# Rev1_0.net
KiCad netlist of a schematic drawn in EAGLE
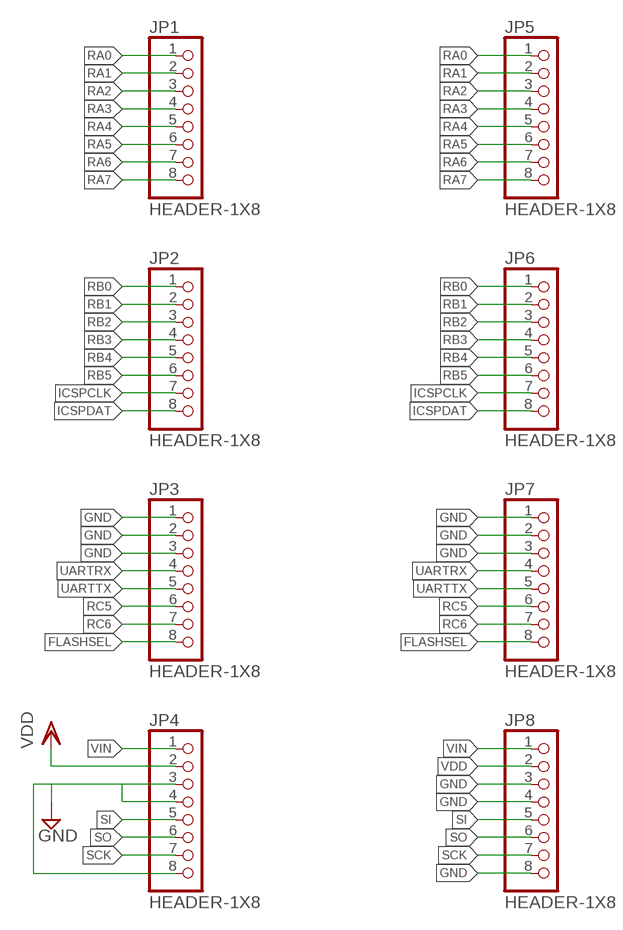
[diagram p0: schematic, sheet 1]

(export (version "E")
  (design (tool "Eeschema 10.0.6"))
  (components
    (comp (ref "JP1")
      (value "HEADER-1X8")
      (footprint "eagle-import:1X08")
      (libsource (lib "eagle-import") (part "HEADER-1X8"))
    )
    (comp (ref "JP2")
      (value "HEADER-1X8")
      (footprint "eagle-import:1X08")
      (libsource (lib "eagle-import") (part "HEADER-1X8"))
    )
    (comp (ref "JP3")
      (value "HEADER-1X8")
      (footprint "eagle-import:1X08")
      (libsource (lib "eagle-import") (part "HEADER-1X8"))
    )
    (comp (ref "JP4")
      (value "HEADER-1X8")
      (footprint "eagle-import:1X08")
      (libsource (lib "eagle-import") (part "HEADER-1X8"))
    )
    (comp (ref "JP5")
      (value "HEADER-1X8")
      (footprint "eagle-import:1X08")
      (libsource (lib "eagle-import") (part "HEADER-1X8"))
    )
    (comp (ref "JP6")
      (value "HEADER-1X8")
      (footprint "eagle-import:1X08")
      (libsource (lib "eagle-import") (part "HEADER-1X8"))
    )
    (comp (ref "JP7")
      (value "HEADER-1X8")
      (footprint "eagle-import:1X08")
      (libsource (lib "eagle-import") (part "HEADER-1X8"))
    )
    (comp (ref "JP8")
      (value "HEADER-1X8")
      (footprint "eagle-import:1X08")
      (libsource (lib "eagle-import") (part "HEADER-1X8"))
    )
  )
  (nets
    (net (code "1") (name "FLASHSEL") (class "Default")
      (node (ref "JP3") (pin "8") (pinfunction "8_8") (pintype "passive"))
      (node (ref "JP7") (pin "8") (pinfunction "8_8") (pintype "passive"))
    )
    (net (code "2") (name "GND") (class "Default")
      (node (ref "JP3") (pin "1") (pinfunction "1_1") (pintype "passive"))
      (node (ref "JP3") (pin "2") (pinfunction "2_2") (pintype "passive"))
      (node (ref "JP3") (pin "3") (pinfunction "3_3") (pintype "passive"))
      (node (ref "JP4") (pin "3") (pinfunction "3_3") (pintype "passive"))
      (node (ref "JP4") (pin "4") (pinfunction "4_4") (pintype "passive"))
      (node (ref "JP4") (pin "8") (pinfunction "8_8") (pintype "passive"))
      (node (ref "JP7") (pin "1") (pinfunction "1_1") (pintype "passive"))
      (node (ref "JP7") (pin "2") (pinfunction "2_2") (pintype "passive"))
      (node (ref "JP7") (pin "3") (pinfunction "3_3") (pintype "passive"))
      (node (ref "JP8") (pin "3") (pinfunction "3_3") (pintype "passive"))
      (node (ref "JP8") (pin "4") (pinfunction "4_4") (pintype "passive"))
      (node (ref "JP8") (pin "8") (pinfunction "8_8") (pintype "passive"))
    )
    (net (code "3") (name "ICSPCLK") (class "Default")
      (node (ref "JP2") (pin "7") (pinfunction "7_7") (pintype "passive"))
      (node (ref "JP6") (pin "7") (pinfunction "7_7") (pintype "passive"))
    )
    (net (code "4") (name "ICSPDAT") (class "Default")
      (node (ref "JP2") (pin "8") (pinfunction "8_8") (pintype "passive"))
      (node (ref "JP6") (pin "8") (pinfunction "8_8") (pintype "passive"))
    )
    (net (code "5") (name "RA0") (class "Default")
      (node (ref "JP1") (pin "1") (pinfunction "1_1") (pintype "passive"))
      (node (ref "JP5") (pin "1") (pinfunction "1_1") (pintype "passive"))
    )
    (net (code "6") (name "RA1") (class "Default")
      (node (ref "JP1") (pin "2") (pinfunction "2_2") (pintype "passive"))
      (node (ref "JP5") (pin "2") (pinfunction "2_2") (pintype "passive"))
    )
    (net (code "7") (name "RA2") (class "Default")
      (node (ref "JP1") (pin "3") (pinfunction "3_3") (pintype "passive"))
      (node (ref "JP5") (pin "3") (pinfunction "3_3") (pintype "passive"))
    )
    (net (code "8") (name "RA3") (class "Default")
      (node (ref "JP1") (pin "4") (pinfunction "4_4") (pintype "passive"))
      (node (ref "JP5") (pin "4") (pinfunction "4_4") (pintype "passive"))
    )
    (net (code "9") (name "RA4") (class "Default")
      (node (ref "JP1") (pin "5") (pinfunction "5_5") (pintype "passive"))
      (node (ref "JP5") (pin "5") (pinfunction "5_5") (pintype "passive"))
    )
    (net (code "10") (name "RA5") (class "Default")
      (node (ref "JP1") (pin "6") (pinfunction "6_6") (pintype "passive"))
      (node (ref "JP5") (pin "6") (pinfunction "6_6") (pintype "passive"))
    )
    (net (code "11") (name "RA6") (class "Default")
      (node (ref "JP1") (pin "7") (pinfunction "7_7") (pintype "passive"))
      (node (ref "JP5") (pin "7") (pinfunction "7_7") (pintype "passive"))
    )
    (net (code "12") (name "RA7") (class "Default")
      (node (ref "JP1") (pin "8") (pinfunction "8_8") (pintype "passive"))
      (node (ref "JP5") (pin "8") (pinfunction "8_8") (pintype "passive"))
    )
    (net (code "13") (name "RB0") (class "Default")
      (node (ref "JP2") (pin "1") (pinfunction "1_1") (pintype "passive"))
      (node (ref "JP6") (pin "1") (pinfunction "1_1") (pintype "passive"))
    )
    (net (code "14") (name "RB1") (class "Default")
      (node (ref "JP2") (pin "2") (pinfunction "2_2") (pintype "passive"))
      (node (ref "JP6") (pin "2") (pinfunction "2_2") (pintype "passive"))
    )
    (net (code "15") (name "RB2") (class "Default")
      (node (ref "JP2") (pin "3") (pinfunction "3_3") (pintype "passive"))
      (node (ref "JP6") (pin "3") (pinfunction "3_3") (pintype "passive"))
    )
    (net (code "16") (name "RB3") (class "Default")
      (node (ref "JP2") (pin "4") (pinfunction "4_4") (pintype "passive"))
      (node (ref "JP6") (pin "4") (pinfunction "4_4") (pintype "passive"))
    )
    (net (code "17") (name "RB4") (class "Default")
      (node (ref "JP2") (pin "5") (pinfunction "5_5") (pintype "passive"))
      (node (ref "JP6") (pin "5") (pinfunction "5_5") (pintype "passive"))
    )
    (net (code "18") (name "RB5") (class "Default")
      (node (ref "JP2") (pin "6") (pinfunction "6_6") (pintype "passive"))
      (node (ref "JP6") (pin "6") (pinfunction "6_6") (pintype "passive"))
    )
    (net (code "19") (name "RC5") (class "Default")
      (node (ref "JP3") (pin "6") (pinfunction "6_6") (pintype "passive"))
      (node (ref "JP7") (pin "6") (pinfunction "6_6") (pintype "passive"))
    )
    (net (code "20") (name "RC6") (class "Default")
      (node (ref "JP3") (pin "7") (pinfunction "7_7") (pintype "passive"))
      (node (ref "JP7") (pin "7") (pinfunction "7_7") (pintype "passive"))
    )
    (net (code "21") (name "SCK") (class "Default")
      (node (ref "JP4") (pin "7") (pinfunction "7_7") (pintype "passive"))
      (node (ref "JP8") (pin "7") (pinfunction "7_7") (pintype "passive"))
    )
    (net (code "22") (name "SI") (class "Default")
      (node (ref "JP4") (pin "5") (pinfunction "5_5") (pintype "passive"))
      (node (ref "JP8") (pin "5") (pinfunction "5_5") (pintype "passive"))
    )
    (net (code "23") (name "SO") (class "Default")
      (node (ref "JP4") (pin "6") (pinfunction "6_6") (pintype "passive"))
      (node (ref "JP8") (pin "6") (pinfunction "6_6") (pintype "passive"))
    )
    (net (code "24") (name "UARTRX") (class "Default")
      (node (ref "JP3") (pin "4") (pinfunction "4_4") (pintype "passive"))
      (node (ref "JP7") (pin "4") (pinfunction "4_4") (pintype "passive"))
    )
    (net (code "25") (name "UARTTX") (class "Default")
      (node (ref "JP3") (pin "5") (pinfunction "5_5") (pintype "passive"))
      (node (ref "JP7") (pin "5") (pinfunction "5_5") (pintype "passive"))
    )
    (net (code "26") (name "VDD") (class "Default")
      (node (ref "JP4") (pin "2") (pinfunction "2_2") (pintype "passive"))
      (node (ref "JP8") (pin "2") (pinfunction "2_2") (pintype "passive"))
    )
    (net (code "27") (name "VIN") (class "Default")
      (node (ref "JP4") (pin "1") (pinfunction "1_1") (pintype "passive"))
      (node (ref "JP8") (pin "1") (pinfunction "1_1") (pintype "passive"))
    )
  )
)
